# 05_CONNECTOR_OUT.net
KiCad netlist of a schematic drawn in Altium Designer
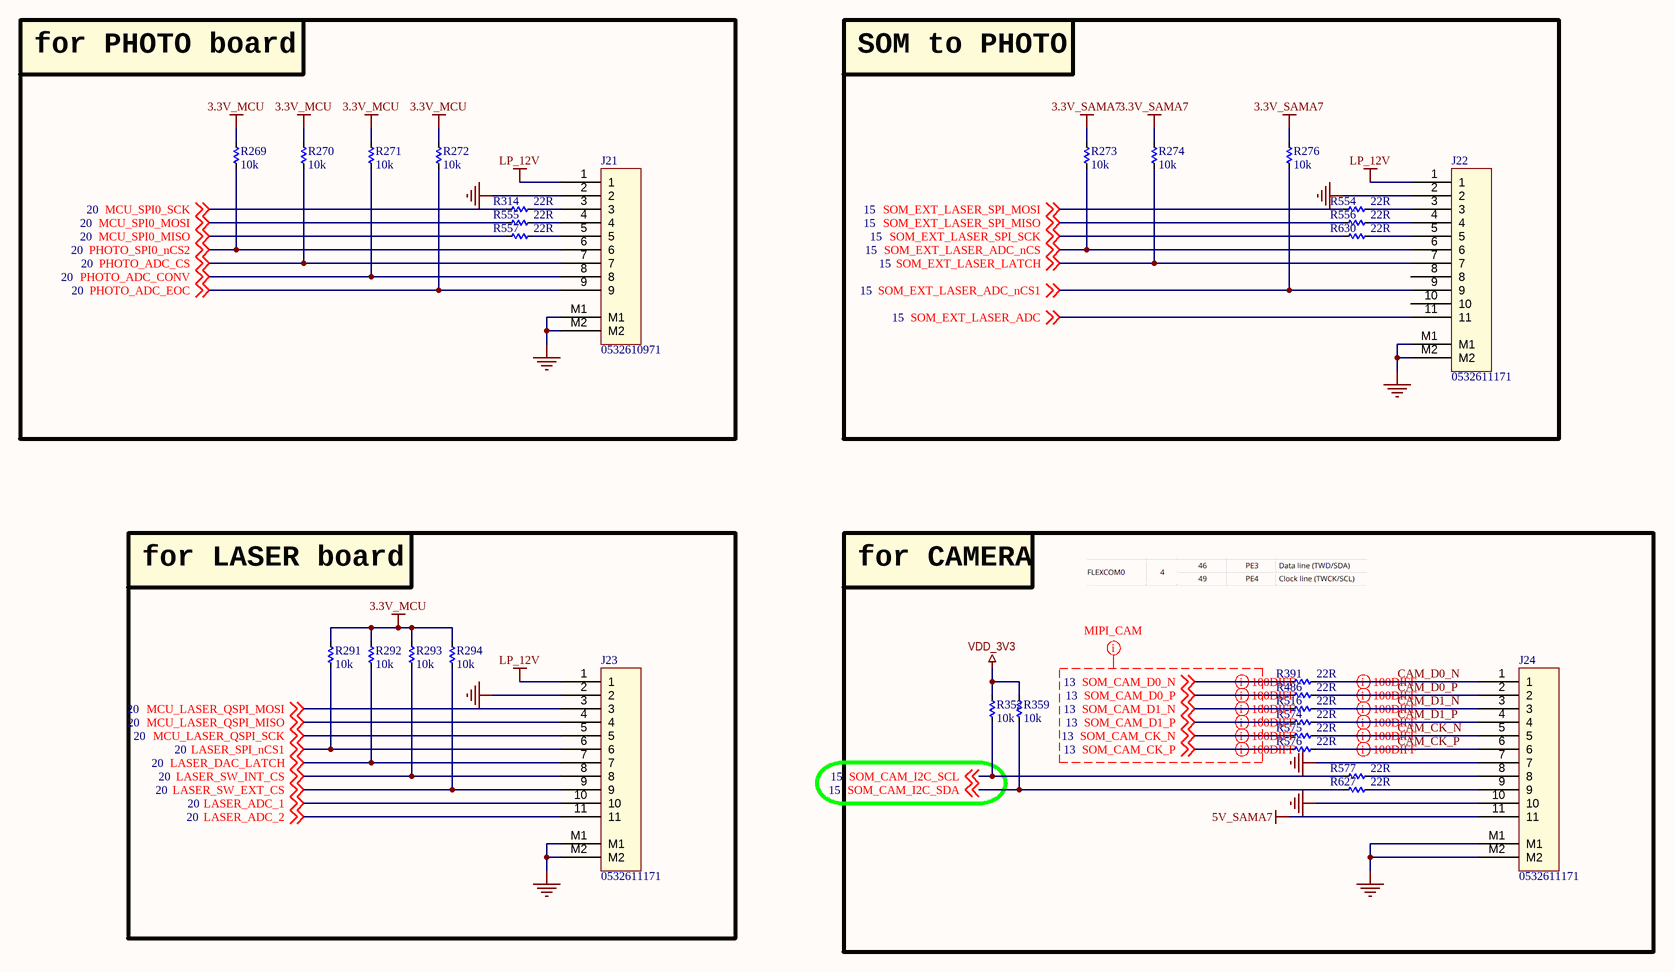
[diagram p0: 05_CONNECTOR_OUT.SchDoc]

(export (version "E")
  (design (tool "Eeschema 10.0.6"))
  (components
    (comp (ref "J21")
      (value "0532610971")
      (footprint "MOLEX_0532610971")
      (libsource (lib "LABLIB") (part "Header 9x1_2M"))
    )
    (comp (ref "J22")
      (value "0532611171")
      (footprint "MOLEX_0532611171")
      (libsource (lib "LABLIB") (part "Header 11x1_2M"))
    )
    (comp (ref "J23")
      (value "0532611171")
      (footprint "MOLEX_0532611171")
      (libsource (lib "LABLIB") (part "Header 11x1_2M"))
    )
    (comp (ref "J24")
      (value "0532611171")
      (footprint "MOLEX_0532611171")
      (libsource (lib "LABLIB") (part "Header 11x1_2M"))
    )
    (comp (ref "R269")
      (value "10k")
      (footprint "RES_C_1005X40")
      (description "RES")
      (libsource (lib "LABLIB") (part "_RES_B_2"))
    )
    (comp (ref "R270")
      (value "10k")
      (footprint "RES_C_1005X40")
      (description "RES")
      (libsource (lib "LABLIB") (part "_RES_B_2"))
    )
    (comp (ref "R271")
      (value "10k")
      (footprint "RES_C_1005X40")
      (description "RES")
      (libsource (lib "LABLIB") (part "_RES_B_2"))
    )
    (comp (ref "R272")
      (value "10k")
      (footprint "RES_C_1005X40")
      (description "RES")
      (libsource (lib "LABLIB") (part "_RES_B_2"))
    )
    (comp (ref "R273")
      (value "10k")
      (footprint "RES_C_1005X40")
      (description "RES")
      (libsource (lib "LABLIB") (part "_RES_B_2"))
    )
    (comp (ref "R274")
      (value "10k")
      (footprint "RES_C_1005X40")
      (description "RES")
      (libsource (lib "LABLIB") (part "_RES_B_2"))
    )
    (comp (ref "R276")
      (value "10k")
      (footprint "RES_C_1005X40")
      (description "RES")
      (libsource (lib "LABLIB") (part "_RES_B_2"))
    )
    (comp (ref "R291")
      (value "10k")
      (footprint "RES_C_1005X40")
      (description "RES")
      (libsource (lib "LABLIB") (part "_RES_B_2"))
    )
    (comp (ref "R292")
      (value "10k")
      (footprint "RES_C_1005X40")
      (description "RES")
      (libsource (lib "LABLIB") (part "_RES_B_2"))
    )
    (comp (ref "R293")
      (value "10k")
      (footprint "RES_C_1005X40")
      (description "RES")
      (libsource (lib "LABLIB") (part "_RES_B_2"))
    )
    (comp (ref "R294")
      (value "10k")
      (footprint "RES_C_1005X40")
      (description "RES")
      (libsource (lib "LABLIB") (part "_RES_B_2"))
    )
    (comp (ref "R314")
      (value "22R")
      (footprint "RES_C_1005X40")
      (description "RES")
      (libsource (lib "LABLIB") (part "_RES_B_2"))
    )
    (comp (ref "R352")
      (value "10k")
      (footprint "RES_C_1005X40")
      (description "RES")
      (libsource (lib "LABLIB") (part "_RES_B_2"))
    )
    (comp (ref "R359")
      (value "10k")
      (footprint "RES_C_1005X40")
      (description "RES")
      (libsource (lib "LABLIB") (part "_RES_B_2"))
    )
    (comp (ref "R391")
      (value "22R")
      (footprint "RES_C_1005X40")
      (description "RES")
      (libsource (lib "LABLIB") (part "_RES_B_2"))
    )
    (comp (ref "R486")
      (value "22R")
      (footprint "RES_C_1005X40")
      (description "RES")
      (libsource (lib "LABLIB") (part "_RES_B_2"))
    )
    (comp (ref "R516")
      (value "22R")
      (footprint "RES_C_1005X40")
      (description "RES")
      (libsource (lib "LABLIB") (part "_RES_B_2"))
    )
    (comp (ref "R554")
      (value "22R")
      (footprint "RES_C_1005X40")
      (description "RES")
      (libsource (lib "LABLIB") (part "_RES_B_2"))
    )
    (comp (ref "R555")
      (value "22R")
      (footprint "RES_C_1005X40")
      (description "RES")
      (libsource (lib "LABLIB") (part "_RES_B_2"))
    )
    (comp (ref "R556")
      (value "22R")
      (footprint "RES_C_1005X40")
      (description "RES")
      (libsource (lib "LABLIB") (part "_RES_B_2"))
    )
    (comp (ref "R557")
      (value "22R")
      (footprint "RES_C_1005X40")
      (description "RES")
      (libsource (lib "LABLIB") (part "_RES_B_2"))
    )
    (comp (ref "R574")
      (value "22R")
      (footprint "RES_C_1005X40")
      (description "RES")
      (libsource (lib "LABLIB") (part "_RES_B_2"))
    )
    (comp (ref "R575")
      (value "22R")
      (footprint "RES_C_1005X40")
      (description "RES")
      (libsource (lib "LABLIB") (part "_RES_B_2"))
    )
    (comp (ref "R576")
      (value "22R")
      (footprint "RES_C_1005X40")
      (description "RES")
      (libsource (lib "LABLIB") (part "_RES_B_2"))
    )
    (comp (ref "R577")
      (value "22R")
      (footprint "RES_C_1005X40")
      (description "RES")
      (libsource (lib "LABLIB") (part "_RES_B_2"))
    )
    (comp (ref "R627")
      (value "22R")
      (footprint "RES_C_1005X40")
      (description "RES")
      (libsource (lib "LABLIB") (part "_RES_B_2"))
    )
    (comp (ref "R630")
      (value "22R")
      (footprint "RES_C_1005X40")
      (description "RES")
      (libsource (lib "LABLIB") (part "_RES_B_2"))
    )
  )
  (nets
    (net (code "1") (name "/CAM_CK_N") (class "Default")
      (node (ref "J24") (pin "5") (pinfunction "5_5") (pintype "passive"))
      (node (ref "R575") (pin "2") (pinfunction "2_2") (pintype "passive"))
    )
    (net (code "2") (name "/CAM_CK_P") (class "Default")
      (node (ref "J24") (pin "6") (pinfunction "6_6") (pintype "passive"))
      (node (ref "R576") (pin "2") (pinfunction "2_2") (pintype "passive"))
    )
    (net (code "3") (name "/CAM_D0_N") (class "Default")
      (node (ref "J24") (pin "1") (pinfunction "1_1") (pintype "passive"))
      (node (ref "R391") (pin "2") (pinfunction "2_2") (pintype "passive"))
    )
    (net (code "4") (name "/CAM_D0_P") (class "Default")
      (node (ref "J24") (pin "2") (pinfunction "2_2") (pintype "passive"))
      (node (ref "R486") (pin "2") (pinfunction "2_2") (pintype "passive"))
    )
    (net (code "5") (name "/CAM_D1_N") (class "Default")
      (node (ref "J24") (pin "3") (pinfunction "3_3") (pintype "passive"))
      (node (ref "R516") (pin "2") (pinfunction "2_2") (pintype "passive"))
    )
    (net (code "6") (name "/CAM_D1_P") (class "Default")
      (node (ref "J24") (pin "4") (pinfunction "4_4") (pintype "passive"))
      (node (ref "R574") (pin "2") (pinfunction "2_2") (pintype "passive"))
    )
    (net (code "7") (name "3.3V_MCU") (class "Default")
      (node (ref "R269") (pin "1") (pinfunction "1_1") (pintype "passive"))
      (node (ref "R270") (pin "1") (pinfunction "1_1") (pintype "passive"))
      (node (ref "R271") (pin "1") (pinfunction "1_1") (pintype "passive"))
      (node (ref "R272") (pin "1") (pinfunction "1_1") (pintype "passive"))
      (node (ref "R291") (pin "1") (pinfunction "1_1") (pintype "passive"))
      (node (ref "R292") (pin "1") (pinfunction "1_1") (pintype "passive"))
      (node (ref "R293") (pin "1") (pinfunction "1_1") (pintype "passive"))
      (node (ref "R294") (pin "1") (pinfunction "1_1") (pintype "passive"))
    )
    (net (code "8") (name "3.3V_SAMA7") (class "Default")
      (node (ref "R273") (pin "1") (pinfunction "1_1") (pintype "passive"))
      (node (ref "R274") (pin "1") (pinfunction "1_1") (pintype "passive"))
      (node (ref "R276") (pin "1") (pinfunction "1_1") (pintype "passive"))
    )
    (net (code "9") (name "5V_SAMA7") (class "Default")
      (node (ref "J24") (pin "11") (pinfunction "11_11") (pintype "passive"))
    )
    (net (code "10") (name "GND") (class "Default")
      (node (ref "J21") (pin "2") (pinfunction "2_2") (pintype "passive"))
      (node (ref "J21") (pin "M1") (pinfunction "M1_M1") (pintype "passive"))
      (node (ref "J21") (pin "M2") (pinfunction "M2_M2") (pintype "passive"))
      (node (ref "J22") (pin "2") (pinfunction "2_2") (pintype "passive"))
      (node (ref "J22") (pin "M1") (pinfunction "M1_M1") (pintype "passive"))
      (node (ref "J22") (pin "M2") (pinfunction "M2_M2") (pintype "passive"))
      (node (ref "J23") (pin "2") (pinfunction "2_2") (pintype "passive"))
      (node (ref "J23") (pin "M1") (pinfunction "M1_M1") (pintype "passive"))
      (node (ref "J23") (pin "M2") (pinfunction "M2_M2") (pintype "passive"))
      (node (ref "J24") (pin "10") (pinfunction "10_10") (pintype "passive"))
      (node (ref "J24") (pin "7") (pinfunction "7_7") (pintype "passive"))
      (node (ref "J24") (pin "M1") (pinfunction "M1_M1") (pintype "passive"))
      (node (ref "J24") (pin "M2") (pinfunction "M2_M2") (pintype "passive"))
    )
    (net (code "11") (name "LASER_ADC_1") (class "Default")
      (node (ref "J23") (pin "10") (pinfunction "10_10") (pintype "passive"))
    )
    (net (code "12") (name "LASER_ADC_2") (class "Default")
      (node (ref "J23") (pin "11") (pinfunction "11_11") (pintype "passive"))
    )
    (net (code "13") (name "LASER_DAC_LATCH") (class "Default")
      (node (ref "J23") (pin "7") (pinfunction "7_7") (pintype "passive"))
      (node (ref "R292") (pin "2") (pinfunction "2_2") (pintype "passive"))
    )
    (net (code "14") (name "LASER_SPI_nCS1") (class "Default")
      (node (ref "J23") (pin "6") (pinfunction "6_6") (pintype "passive"))
      (node (ref "R291") (pin "2") (pinfunction "2_2") (pintype "passive"))
    )
    (net (code "15") (name "LASER_SW_EXT_CS") (class "Default")
      (node (ref "J23") (pin "9") (pinfunction "9_9") (pintype "passive"))
      (node (ref "R294") (pin "2") (pinfunction "2_2") (pintype "passive"))
    )
    (net (code "16") (name "LASER_SW_INT_CS") (class "Default")
      (node (ref "J23") (pin "8") (pinfunction "8_8") (pintype "passive"))
      (node (ref "R293") (pin "2") (pinfunction "2_2") (pintype "passive"))
    )
    (net (code "17") (name "LP_12V") (class "Default")
      (node (ref "J21") (pin "1") (pinfunction "1_1") (pintype "passive"))
      (node (ref "J22") (pin "1") (pinfunction "1_1") (pintype "passive"))
      (node (ref "J23") (pin "1") (pinfunction "1_1") (pintype "passive"))
    )
    (net (code "18") (name "MCU_LASER_QSPI_MISO") (class "Default")
      (node (ref "J23") (pin "4") (pinfunction "4_4") (pintype "passive"))
    )
    (net (code "19") (name "MCU_LASER_QSPI_MOSI") (class "Default")
      (node (ref "J23") (pin "3") (pinfunction "3_3") (pintype "passive"))
    )
    (net (code "20") (name "MCU_LASER_QSPI_SCK") (class "Default")
      (node (ref "J23") (pin "5") (pinfunction "5_5") (pintype "passive"))
    )
    (net (code "21") (name "MCU_SPI0_MISO") (class "Default")
      (node (ref "R557") (pin "1") (pinfunction "1_1") (pintype "passive"))
    )
    (net (code "22") (name "MCU_SPI0_MOSI") (class "Default")
      (node (ref "R555") (pin "1") (pinfunction "1_1") (pintype "passive"))
    )
    (net (code "23") (name "MCU_SPI0_SCK") (class "Default")
      (node (ref "R314") (pin "1") (pinfunction "1_1") (pintype "passive"))
    )
    (net (code "24") (name "Net-(J21-Pad3)") (class "Default")
      (node (ref "J21") (pin "3") (pinfunction "3_3") (pintype "passive"))
      (node (ref "R314") (pin "2") (pinfunction "2_2") (pintype "passive"))
    )
    (net (code "25") (name "Net-(J21-Pad4)") (class "Default")
      (node (ref "J21") (pin "4") (pinfunction "4_4") (pintype "passive"))
      (node (ref "R555") (pin "2") (pinfunction "2_2") (pintype "passive"))
    )
    (net (code "26") (name "Net-(J21-Pad5)") (class "Default")
      (node (ref "J21") (pin "5") (pinfunction "5_5") (pintype "passive"))
      (node (ref "R557") (pin "2") (pinfunction "2_2") (pintype "passive"))
    )
    (net (code "27") (name "Net-(J22-Pad3)") (class "Default")
      (node (ref "J22") (pin "3") (pinfunction "3_3") (pintype "passive"))
      (node (ref "R554") (pin "2") (pinfunction "2_2") (pintype "passive"))
    )
    (net (code "28") (name "Net-(J22-Pad4)") (class "Default")
      (node (ref "J22") (pin "4") (pinfunction "4_4") (pintype "passive"))
      (node (ref "R556") (pin "2") (pinfunction "2_2") (pintype "passive"))
    )
    (net (code "29") (name "Net-(J22-Pad5)") (class "Default")
      (node (ref "J22") (pin "5") (pinfunction "5_5") (pintype "passive"))
      (node (ref "R630") (pin "2") (pinfunction "2_2") (pintype "passive"))
    )
    (net (code "30") (name "Net-(J24-Pad8)") (class "Default")
      (node (ref "J24") (pin "8") (pinfunction "8_8") (pintype "passive"))
      (node (ref "R577") (pin "2") (pinfunction "2_2") (pintype "passive"))
    )
    (net (code "31") (name "Net-(J24-Pad9)") (class "Default")
      (node (ref "J24") (pin "9") (pinfunction "9_9") (pintype "passive"))
      (node (ref "R627") (pin "2") (pinfunction "2_2") (pintype "passive"))
    )
    (net (code "32") (name "PHOTO_ADC_CONV") (class "Default")
      (node (ref "J21") (pin "8") (pinfunction "8_8") (pintype "passive"))
      (node (ref "R271") (pin "2") (pinfunction "2_2") (pintype "passive"))
    )
    (net (code "33") (name "PHOTO_ADC_CS") (class "Default")
      (node (ref "J21") (pin "7") (pinfunction "7_7") (pintype "passive"))
      (node (ref "R270") (pin "2") (pinfunction "2_2") (pintype "passive"))
    )
    (net (code "34") (name "PHOTO_ADC_EOC") (class "Default")
      (node (ref "J21") (pin "9") (pinfunction "9_9") (pintype "passive"))
      (node (ref "R272") (pin "2") (pinfunction "2_2") (pintype "passive"))
    )
    (net (code "35") (name "PHOTO_SPI0_nCS2") (class "Default")
      (node (ref "J21") (pin "6") (pinfunction "6_6") (pintype "passive"))
      (node (ref "R269") (pin "2") (pinfunction "2_2") (pintype "passive"))
    )
    (net (code "36") (name "SOM_CAM_CK_N") (class "Default")
      (node (ref "R575") (pin "1") (pinfunction "1_1") (pintype "passive"))
    )
    (net (code "37") (name "SOM_CAM_CK_P") (class "Default")
      (node (ref "R576") (pin "1") (pinfunction "1_1") (pintype "passive"))
    )
    (net (code "38") (name "SOM_CAM_D0_N") (class "Default")
      (node (ref "R391") (pin "1") (pinfunction "1_1") (pintype "passive"))
    )
    (net (code "39") (name "SOM_CAM_D0_P") (class "Default")
      (node (ref "R486") (pin "1") (pinfunction "1_1") (pintype "passive"))
    )
    (net (code "40") (name "SOM_CAM_D1_N") (class "Default")
      (node (ref "R516") (pin "1") (pinfunction "1_1") (pintype "passive"))
    )
    (net (code "41") (name "SOM_CAM_D1_P") (class "Default")
      (node (ref "R574") (pin "1") (pinfunction "1_1") (pintype "passive"))
    )
    (net (code "42") (name "SOM_CAM_I2C_SCL") (class "Default")
      (node (ref "R352") (pin "2") (pinfunction "2_2") (pintype "passive"))
      (node (ref "R577") (pin "1") (pinfunction "1_1") (pintype "passive"))
    )
    (net (code "43") (name "SOM_CAM_I2C_SDA") (class "Default")
      (node (ref "R359") (pin "2") (pinfunction "2_2") (pintype "passive"))
      (node (ref "R627") (pin "1") (pinfunction "1_1") (pintype "passive"))
    )
    (net (code "44") (name "SOM_EXT_LASER_ADC") (class "Default")
      (node (ref "J22") (pin "11") (pinfunction "11_11") (pintype "passive"))
    )
    (net (code "45") (name "SOM_EXT_LASER_ADC_nCS") (class "Default")
      (node (ref "J22") (pin "6") (pinfunction "6_6") (pintype "passive"))
      (node (ref "R273") (pin "2") (pinfunction "2_2") (pintype "passive"))
    )
    (net (code "46") (name "SOM_EXT_LASER_ADC_nCS1") (class "Default")
      (node (ref "J22") (pin "9") (pinfunction "9_9") (pintype "passive"))
      (node (ref "R276") (pin "2") (pinfunction "2_2") (pintype "passive"))
    )
    (net (code "47") (name "SOM_EXT_LASER_LATCH") (class "Default")
      (node (ref "J22") (pin "7") (pinfunction "7_7") (pintype "passive"))
      (node (ref "R274") (pin "2") (pinfunction "2_2") (pintype "passive"))
    )
    (net (code "48") (name "SOM_EXT_LASER_SPI_MISO") (class "Default")
      (node (ref "R556") (pin "1") (pinfunction "1_1") (pintype "passive"))
    )
    (net (code "49") (name "SOM_EXT_LASER_SPI_MOSI") (class "Default")
      (node (ref "R554") (pin "1") (pinfunction "1_1") (pintype "passive"))
    )
    (net (code "50") (name "SOM_EXT_LASER_SPI_SCK") (class "Default")
      (node (ref "R630") (pin "1") (pinfunction "1_1") (pintype "passive"))
    )
    (net (code "51") (name "VDD_3V3") (class "Default")
      (node (ref "R352") (pin "1") (pinfunction "1_1") (pintype "passive"))
      (node (ref "R359") (pin "1") (pinfunction "1_1") (pintype "passive"))
    )
    (net (code "52") (name "unconnected-(J22-Pad8)") (class "Default")
      (node (ref "J22") (pin "8") (pinfunction "8_8") (pintype "passive"))
    )
    (net (code "53") (name "unconnected-(J22-Pad10)") (class "Default")
      (node (ref "J22") (pin "10") (pinfunction "10_10") (pintype "passive"))
    )
  )
)
